# atividade2.net
KiCad netlist of a schematic drawn in EAGLE
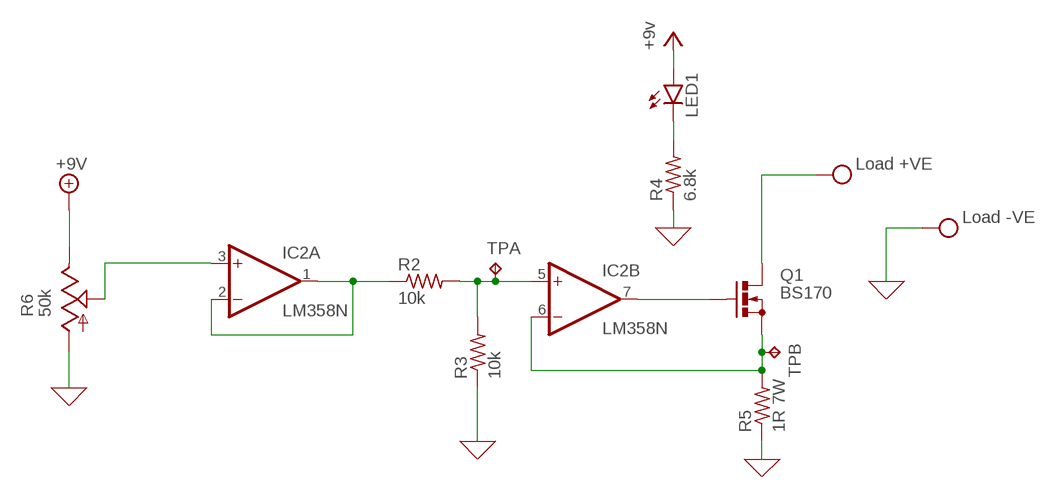
[diagram p0: schematic, sheet 1]

(export (version "E")
  (design (tool "Eeschema 10.0.6"))
  (components
    (comp (ref "IC2")
      (value "LM358N")
      (footprint "eagle-import:DIL08")
      (libsource (lib "eagle-import") (part "LM358N"))
    )
    (comp (ref "LED1")
      (value "LED5MM")
      (footprint "eagle-import:LED5MM")
      (libsource (lib "eagle-import") (part "LED5MM"))
    )
    (comp (ref "Q1")
      (value "BS170")
      (footprint "eagle-import:SOT54E")
      (libsource (lib "eagle-import") (part "BS170"))
    )
    (comp (ref "R2")
      (value "10k")
      (footprint "eagle-import:0204V")
      (libsource (lib "eagle-import") (part "R-US_0204/2V"))
    )
    (comp (ref "R3")
      (value "10k")
      (footprint "eagle-import:0204V")
      (libsource (lib "eagle-import") (part "R-US_0204/2V"))
    )
    (comp (ref "R4")
      (value "6.8k")
      (footprint "eagle-import:0204V")
      (libsource (lib "eagle-import") (part "R-US_0204/2V"))
    )
    (comp (ref "R5")
      (value "1R 7W")
      (footprint "eagle-import:0204V")
      (libsource (lib "eagle-import") (part "R-US_0204/2V"))
    )
    (comp (ref "R6")
      (value "50k")
      (footprint "eagle-import:EVUFXM")
      (libsource (lib "eagle-import") (part "US-EVUMF3"))
    )
    (comp (ref "TPA")
      (value "TPB1,27")
      (footprint "eagle-import:B1,27")
      (libsource (lib "eagle-import") (part "TPB1,27"))
    )
    (comp (ref "TPB")
      (value "TPB1,27")
      (footprint "eagle-import:B1,27")
      (libsource (lib "eagle-import") (part "TPB1,27"))
    )
  )
  (nets
    (net (code "1") (name "+9V") (class "Default")
      (node (ref "R6") (pin "3") (pinfunction "E_3") (pintype "passive"))
    )
    (net (code "2") (name "+9v") (class "Default")
      (node (ref "LED1") (pin "A") (pinfunction "A_A") (pintype "passive"))
    )
    (net (code "3") (name "GND") (class "Default")
      (node (ref "R3") (pin "1") (pinfunction "1_1") (pintype "passive"))
      (node (ref "R4") (pin "1") (pinfunction "1_1") (pintype "passive"))
      (node (ref "R5") (pin "1") (pinfunction "1_1") (pintype "passive"))
      (node (ref "R6") (pin "1") (pinfunction "A_1") (pintype "passive"))
    )
    (net (code "4") (name "Load +VE") (class "Default")
      (node (ref "Q1") (pin "D") (pinfunction "D_D") (pintype "passive"))
    )
    (net (code "5") (name "Net-(IC2A-+IN)") (class "Default")
      (node (ref "IC2") (pin "3") (pinfunction "+IN_3") (pintype "input"))
      (node (ref "R6") (pin "2") (pinfunction "S_2") (pintype "passive"))
    )
    (net (code "6") (name "Net-(IC2A--IN)") (class "Default")
      (node (ref "IC2") (pin "1") (pinfunction "OUT_1") (pintype "output"))
      (node (ref "IC2") (pin "2") (pinfunction "-IN_2") (pintype "input"))
      (node (ref "R2") (pin "1") (pinfunction "1_1") (pintype "passive"))
    )
    (net (code "7") (name "Net-(IC2B-+IN)") (class "Default")
      (node (ref "IC2") (pin "5") (pinfunction "+IN_5") (pintype "input"))
      (node (ref "R2") (pin "2") (pinfunction "2_2") (pintype "passive"))
      (node (ref "R3") (pin "2") (pinfunction "2_2") (pintype "passive"))
      (node (ref "TPA") (pin "TP") (pinfunction "TP_TP") (pintype "input"))
    )
    (net (code "8") (name "Net-(IC2B--IN)") (class "Default")
      (node (ref "IC2") (pin "6") (pinfunction "-IN_6") (pintype "input"))
      (node (ref "Q1") (pin "S") (pinfunction "S_S") (pintype "passive"))
      (node (ref "R5") (pin "2") (pinfunction "2_2") (pintype "passive"))
      (node (ref "TPB") (pin "TP") (pinfunction "TP_TP") (pintype "input"))
    )
    (net (code "9") (name "Net-(IC2B-OUT)") (class "Default")
      (node (ref "IC2") (pin "7") (pinfunction "OUT_7") (pintype "output"))
      (node (ref "Q1") (pin "G") (pinfunction "G_G") (pintype "passive"))
    )
    (net (code "10") (name "Net-(LED1-C)") (class "Default")
      (node (ref "LED1") (pin "K") (pinfunction "C_K") (pintype "passive"))
      (node (ref "R4") (pin "2") (pinfunction "2_2") (pintype "passive"))
    )
  )
)
